# IO_top_board.net
KiCad netlist of a schematic drawn in EAGLE
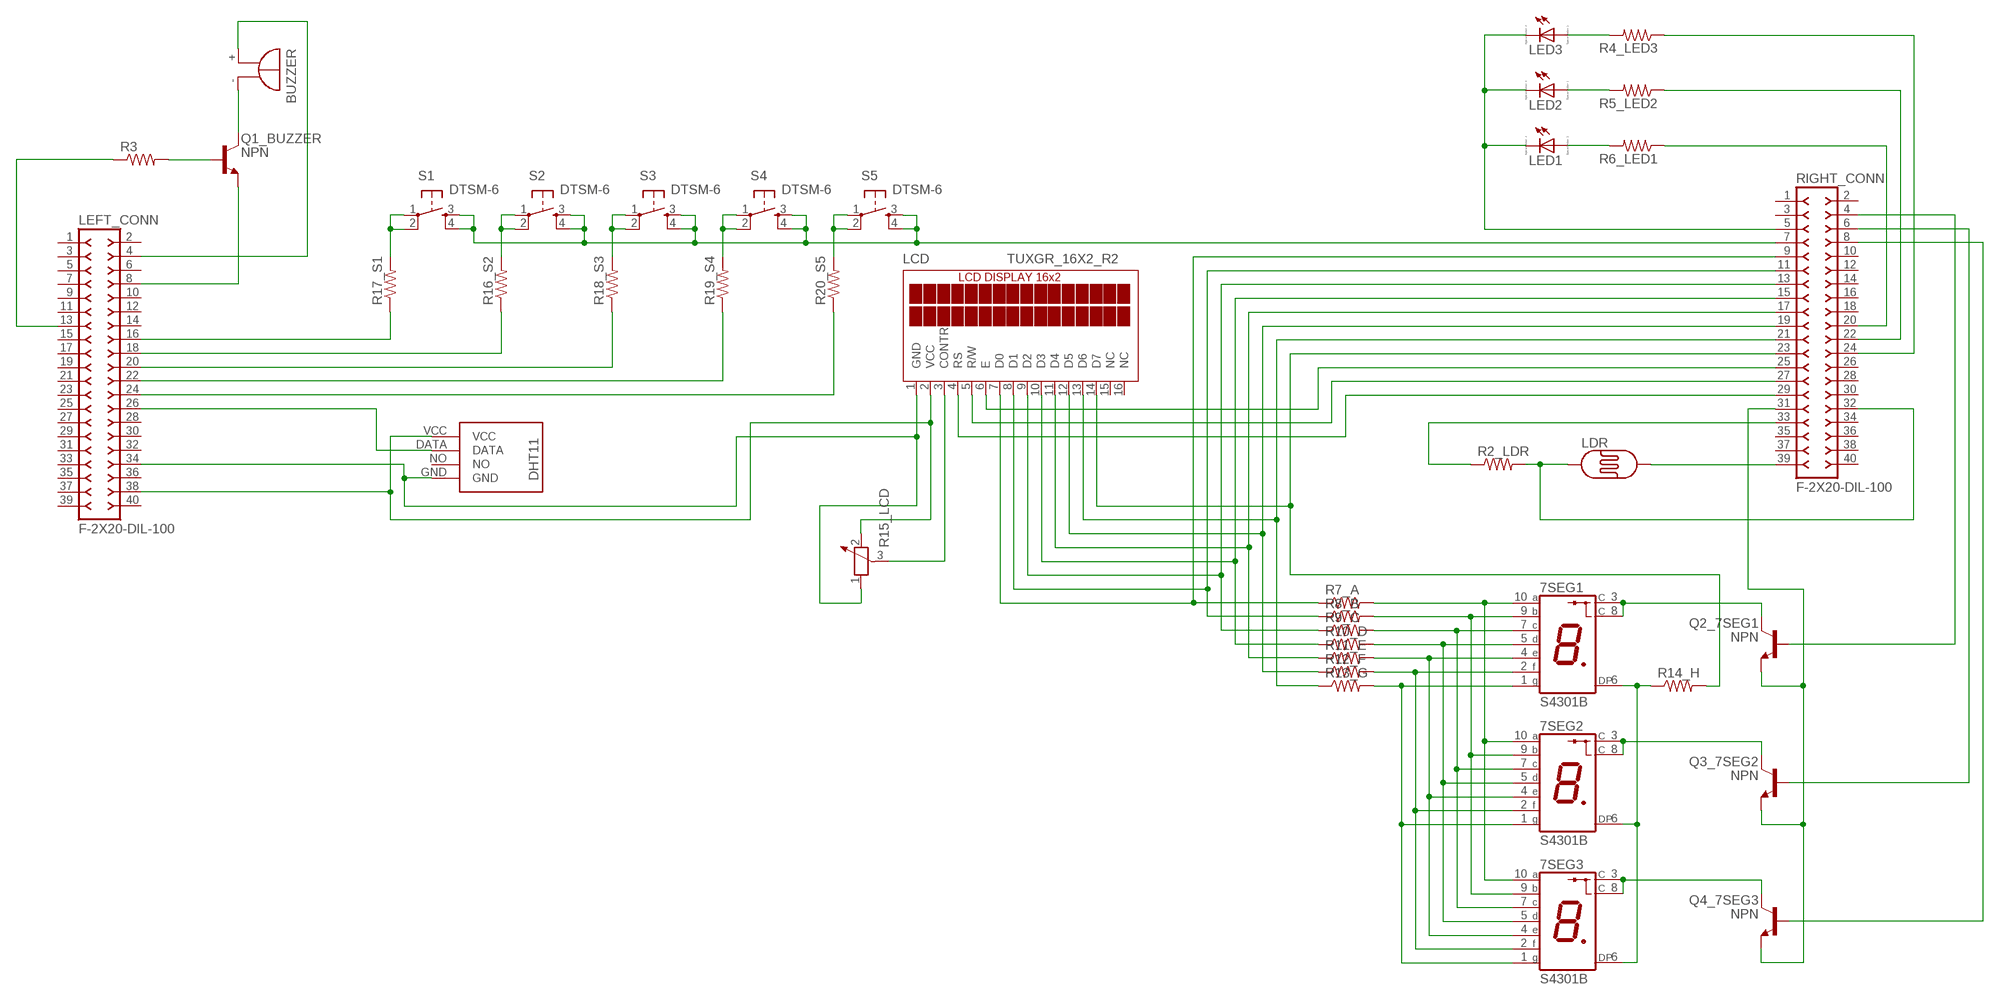
[diagram p0: schematic, sheet 1]

(export (version "E")
  (design (tool "Eeschema 10.0.6"))
  (components
    (comp (ref "7SEG1")
      (value "S4301B")
      (footprint "eagle-import:S4301B")
      (libsource (lib "eagle-import") (part "S4301B"))
    )
    (comp (ref "7SEG2")
      (value "S4301B")
      (footprint "eagle-import:S4301B")
      (libsource (lib "eagle-import") (part "S4301B"))
    )
    (comp (ref "7SEG3")
      (value "S4301B")
      (footprint "eagle-import:S4301B")
      (libsource (lib "eagle-import") (part "S4301B"))
    )
    (comp (ref "BUZZER")
      (value "EB2209A")
      (footprint "eagle-import:EB2209A")
      (libsource (lib "eagle-import") (part "EB2209A"))
    )
    (comp (ref "LCD")
      (value "TUXGR_16X2_R2")
      (footprint "eagle-import:TUXGR_16X2_R2")
      (libsource (lib "eagle-import") (part "TUXGR_16X2_R2"))
    )
    (comp (ref "LDR")
      (value "PHOTOCELLONB")
      (footprint "eagle-import:ON_BOARD")
      (libsource (lib "eagle-import") (part "PHOTOCELLONB"))
    )
    (comp (ref "LED1")
      (value "LED_ELD260")
      (footprint "eagle-import:LED_LD260")
      (libsource (lib "eagle-import") (part "LED_ELD260"))
    )
    (comp (ref "LED2")
      (value "LED_ELD260")
      (footprint "eagle-import:LED_LD260")
      (libsource (lib "eagle-import") (part "LED_ELD260"))
    )
    (comp (ref "LED3")
      (value "LED_ELD260")
      (footprint "eagle-import:LED_LD260")
      (libsource (lib "eagle-import") (part "LED_ELD260"))
    )
    (comp (ref "LEFT_CONN")
      (value "F-2X20-DIL-100")
      (footprint "eagle-import:DIL-100-2X20")
      (libsource (lib "eagle-import") (part "F-2X20-DIL-100"))
    )
    (comp (ref "Q1_BUZZER")
      (value "NPN")
      (footprint "eagle-import:SC70")
      (libsource (lib "eagle-import") (part "NPNSC-70_"))
    )
    (comp (ref "Q2_7SEG1")
      (value "NPN")
      (footprint "eagle-import:SC70")
      (libsource (lib "eagle-import") (part "NPNSC-70_"))
    )
    (comp (ref "Q3_7SEG2")
      (value "NPN")
      (footprint "eagle-import:SC70")
      (libsource (lib "eagle-import") (part "NPNSC-70_"))
    )
    (comp (ref "Q4_7SEG3")
      (value "NPN")
      (footprint "eagle-import:SC70")
      (libsource (lib "eagle-import") (part "NPNSC-70_"))
    )
    (comp (ref "R2_LDR")
      (value "R-US_0204/5")
      (footprint "eagle-import:0204_5")
      (libsource (lib "eagle-import") (part "R-US_0204/5"))
    )
    (comp (ref "R3")
      (value "R-US_0204/5")
      (footprint "eagle-import:0204_5")
      (libsource (lib "eagle-import") (part "R-US_0204/5"))
    )
    (comp (ref "R4_LED3")
      (value "R-US_0204/5")
      (footprint "eagle-import:0204_5")
      (libsource (lib "eagle-import") (part "R-US_0204/5"))
    )
    (comp (ref "R5_LED2")
      (value "R-US_0204/5")
      (footprint "eagle-import:0204_5")
      (libsource (lib "eagle-import") (part "R-US_0204/5"))
    )
    (comp (ref "R6_LED1")
      (value "R-US_0204/5")
      (footprint "eagle-import:0204_5")
      (libsource (lib "eagle-import") (part "R-US_0204/5"))
    )
    (comp (ref "R7_A")
      (value "R-US_0204/5")
      (footprint "eagle-import:0204_5")
      (libsource (lib "eagle-import") (part "R-US_0204/5"))
    )
    (comp (ref "R8_B")
      (value "R-US_0204/5")
      (footprint "eagle-import:0204_5")
      (libsource (lib "eagle-import") (part "R-US_0204/5"))
    )
    (comp (ref "R9_C")
      (value "R-US_0204/5")
      (footprint "eagle-import:0204_5")
      (libsource (lib "eagle-import") (part "R-US_0204/5"))
    )
    (comp (ref "R10_D")
      (value "R-US_0204/5")
      (footprint "eagle-import:0204_5")
      (libsource (lib "eagle-import") (part "R-US_0204/5"))
    )
    (comp (ref "R11_E")
      (value "R-US_0204/5")
      (footprint "eagle-import:0204_5")
      (libsource (lib "eagle-import") (part "R-US_0204/5"))
    )
    (comp (ref "R12_F")
      (value "R-US_0204/5")
      (footprint "eagle-import:0204_5")
      (libsource (lib "eagle-import") (part "R-US_0204/5"))
    )
    (comp (ref "R13_G")
      (value "R-US_0204/5")
      (footprint "eagle-import:0204_5")
      (libsource (lib "eagle-import") (part "R-US_0204/5"))
    )
    (comp (ref "R14_H")
      (value "R-US_0204/5")
      (footprint "eagle-import:0204_5")
      (libsource (lib "eagle-import") (part "R-US_0204/5"))
    )
    (comp (ref "R15_LCD")
      (value "POTENTIOMETER_PT-10")
      (footprint "eagle-import:PT-10")
      (libsource (lib "eagle-import") (part "POTENTIOMETER_PT-10"))
    )
    (comp (ref "R16_S2")
      (value "R-US_0204/5")
      (footprint "eagle-import:0204_5")
      (libsource (lib "eagle-import") (part "R-US_0204/5"))
    )
    (comp (ref "R17_S1")
      (value "R-US_0204/5")
      (footprint "eagle-import:0204_5")
      (libsource (lib "eagle-import") (part "R-US_0204/5"))
    )
    (comp (ref "R18_S3")
      (value "R-US_0204/5")
      (footprint "eagle-import:0204_5")
      (libsource (lib "eagle-import") (part "R-US_0204/5"))
    )
    (comp (ref "R19_S4")
      (value "R-US_0204/5")
      (footprint "eagle-import:0204_5")
      (libsource (lib "eagle-import") (part "R-US_0204/5"))
    )
    (comp (ref "R20_S5")
      (value "R-US_0204/5")
      (footprint "eagle-import:0204_5")
      (libsource (lib "eagle-import") (part "R-US_0204/5"))
    )
    (comp (ref "RIGHT_CONN")
      (value "F-2X20-DIL-100")
      (footprint "eagle-import:DIL-100-2X20")
      (libsource (lib "eagle-import") (part "F-2X20-DIL-100"))
    )
    (comp (ref "S1")
      (value "DTSM-6")
      (footprint "eagle-import:DTSM-6")
      (libsource (lib "eagle-import") (part "DTSM-6"))
    )
    (comp (ref "S2")
      (value "DTSM-6")
      (footprint "eagle-import:DTSM-6")
      (libsource (lib "eagle-import") (part "DTSM-6"))
    )
    (comp (ref "S3")
      (value "DTSM-6")
      (footprint "eagle-import:DTSM-6")
      (libsource (lib "eagle-import") (part "DTSM-6"))
    )
    (comp (ref "S4")
      (value "DTSM-6")
      (footprint "eagle-import:DTSM-6")
      (libsource (lib "eagle-import") (part "DTSM-6"))
    )
    (comp (ref "S5")
      (value "DTSM-6")
      (footprint "eagle-import:DTSM-6")
      (libsource (lib "eagle-import") (part "DTSM-6"))
    )
    (comp (ref "U$1")
      (value "DHT11-PION.")
      (footprint "eagle-import:DHT11-PION.")
      (libsource (lib "eagle-import") (part "DHT11-PION."))
    )
  )
  (nets
    (net (code "1") (name "Net-(7SEG1-A)") (class "Default")
      (node (ref "7SEG1") (pin "10") (pinfunction "A_10") (pintype "passive"))
      (node (ref "7SEG2") (pin "10") (pinfunction "A_10") (pintype "passive"))
      (node (ref "7SEG3") (pin "10") (pinfunction "A_10") (pintype "passive"))
      (node (ref "R7_A") (pin "2") (pinfunction "2_2") (pintype "passive"))
    )
    (net (code "2") (name "Net-(7SEG1-B)") (class "Default")
      (node (ref "7SEG1") (pin "9") (pinfunction "B_9") (pintype "passive"))
      (node (ref "7SEG2") (pin "9") (pinfunction "B_9") (pintype "passive"))
      (node (ref "7SEG3") (pin "9") (pinfunction "B_9") (pintype "passive"))
      (node (ref "R8_B") (pin "2") (pinfunction "2_2") (pintype "passive"))
    )
    (net (code "3") (name "Net-(7SEG1-C-Pad7)") (class "Default")
      (node (ref "7SEG1") (pin "7") (pinfunction "C_7") (pintype "passive"))
      (node (ref "7SEG2") (pin "7") (pinfunction "C_7") (pintype "passive"))
      (node (ref "7SEG3") (pin "7") (pinfunction "C_7") (pintype "passive"))
      (node (ref "R9_C") (pin "2") (pinfunction "2_2") (pintype "passive"))
    )
    (net (code "4") (name "Net-(7SEG1-D)") (class "Default")
      (node (ref "7SEG1") (pin "5") (pinfunction "D_5") (pintype "passive"))
      (node (ref "7SEG2") (pin "5") (pinfunction "D_5") (pintype "passive"))
      (node (ref "7SEG3") (pin "5") (pinfunction "D_5") (pintype "passive"))
      (node (ref "R10_D") (pin "2") (pinfunction "2_2") (pintype "passive"))
    )
    (net (code "5") (name "Net-(7SEG1-DP)") (class "Default")
      (node (ref "7SEG1") (pin "6") (pinfunction "DP_6") (pintype "passive"))
      (node (ref "7SEG2") (pin "6") (pinfunction "DP_6") (pintype "passive"))
      (node (ref "7SEG3") (pin "6") (pinfunction "DP_6") (pintype "passive"))
      (node (ref "R14_H") (pin "1") (pinfunction "1_1") (pintype "passive"))
    )
    (net (code "6") (name "Net-(7SEG1-E)") (class "Default")
      (node (ref "7SEG1") (pin "4") (pinfunction "E_4") (pintype "passive"))
      (node (ref "7SEG2") (pin "4") (pinfunction "E_4") (pintype "passive"))
      (node (ref "7SEG3") (pin "4") (pinfunction "E_4") (pintype "passive"))
      (node (ref "R11_E") (pin "2") (pinfunction "2_2") (pintype "passive"))
    )
    (net (code "7") (name "Net-(7SEG1-F)") (class "Default")
      (node (ref "7SEG1") (pin "2") (pinfunction "F_2") (pintype "passive"))
      (node (ref "7SEG2") (pin "2") (pinfunction "F_2") (pintype "passive"))
      (node (ref "7SEG3") (pin "2") (pinfunction "F_2") (pintype "passive"))
      (node (ref "R12_F") (pin "2") (pinfunction "2_2") (pintype "passive"))
    )
    (net (code "8") (name "Net-(7SEG1-G)") (class "Default")
      (node (ref "7SEG1") (pin "1") (pinfunction "G_1") (pintype "passive"))
      (node (ref "7SEG2") (pin "1") (pinfunction "G_1") (pintype "passive"))
      (node (ref "7SEG3") (pin "1") (pinfunction "G_1") (pintype "passive"))
      (node (ref "R13_G") (pin "2") (pinfunction "2_2") (pintype "passive"))
    )
    (net (code "9") (name "Net-(BUZZER-Pad+)") (class "Default")
      (node (ref "BUZZER") (pin "+") (pinfunction "+_+") (pintype "passive"))
      (node (ref "LEFT_CONN") (pin "4") (pinfunction "4_4") (pintype "passive"))
    )
    (net (code "10") (name "Net-(LCD-CONTR)") (class "Default")
      (node (ref "LCD") (pin "3") (pinfunction "CONTR_3") (pintype "input"))
      (node (ref "R15_LCD") (pin "3") (pinfunction "3_3") (pintype "passive"))
    )
    (net (code "11") (name "Net-(LCD-D0)") (class "Default")
      (node (ref "LCD") (pin "7") (pinfunction "D0_7") (pintype "input"))
      (node (ref "R7_A") (pin "1") (pinfunction "1_1") (pintype "passive"))
      (node (ref "RIGHT_CONN") (pin "9") (pinfunction "9_9") (pintype "passive"))
    )
    (net (code "12") (name "Net-(LCD-D1)") (class "Default")
      (node (ref "LCD") (pin "8") (pinfunction "D1_8") (pintype "input"))
      (node (ref "R8_B") (pin "1") (pinfunction "1_1") (pintype "passive"))
      (node (ref "RIGHT_CONN") (pin "11") (pinfunction "11_11") (pintype "passive"))
    )
    (net (code "13") (name "Net-(LCD-D2)") (class "Default")
      (node (ref "LCD") (pin "9") (pinfunction "D2_9") (pintype "input"))
      (node (ref "R9_C") (pin "1") (pinfunction "1_1") (pintype "passive"))
      (node (ref "RIGHT_CONN") (pin "13") (pinfunction "13_13") (pintype "passive"))
    )
    (net (code "14") (name "Net-(LCD-D3)") (class "Default")
      (node (ref "LCD") (pin "10") (pinfunction "D3_10") (pintype "input"))
      (node (ref "R10_D") (pin "1") (pinfunction "1_1") (pintype "passive"))
      (node (ref "RIGHT_CONN") (pin "15") (pinfunction "15_15") (pintype "passive"))
    )
    (net (code "15") (name "Net-(LCD-D4)") (class "Default")
      (node (ref "LCD") (pin "11") (pinfunction "D4_11") (pintype "input"))
      (node (ref "R11_E") (pin "1") (pinfunction "1_1") (pintype "passive"))
      (node (ref "RIGHT_CONN") (pin "17") (pinfunction "17_17") (pintype "passive"))
    )
    (net (code "16") (name "Net-(LCD-D5)") (class "Default")
      (node (ref "LCD") (pin "12") (pinfunction "D5_12") (pintype "input"))
      (node (ref "R12_F") (pin "1") (pinfunction "1_1") (pintype "passive"))
      (node (ref "RIGHT_CONN") (pin "19") (pinfunction "19_19") (pintype "passive"))
    )
    (net (code "17") (name "Net-(LCD-D6)") (class "Default")
      (node (ref "LCD") (pin "13") (pinfunction "D6_13") (pintype "input"))
      (node (ref "R13_G") (pin "1") (pinfunction "1_1") (pintype "passive"))
      (node (ref "RIGHT_CONN") (pin "21") (pinfunction "21_21") (pintype "passive"))
    )
    (net (code "18") (name "Net-(LCD-D7)") (class "Default")
      (node (ref "LCD") (pin "14") (pinfunction "D7_14") (pintype "input"))
      (node (ref "R14_H") (pin "2") (pinfunction "2_2") (pintype "passive"))
      (node (ref "RIGHT_CONN") (pin "23") (pinfunction "23_23") (pintype "passive"))
    )
    (net (code "19") (name "Net-(LCD-E)") (class "Default")
      (node (ref "LCD") (pin "6") (pinfunction "E_6") (pintype "input"))
      (node (ref "RIGHT_CONN") (pin "25") (pinfunction "25_25") (pintype "passive"))
    )
    (net (code "20") (name "Net-(LCD-GND)") (class "Default")
      (node (ref "LCD") (pin "1") (pinfunction "GND_1") (pintype "power_in"))
      (node (ref "LEFT_CONN") (pin "34") (pinfunction "34_34") (pintype "passive"))
      (node (ref "R15_LCD") (pin "1") (pinfunction "1_1") (pintype "passive"))
      (node (ref "U$1") (pin "GND") (pinfunction "GND_GND") (pintype "bidirectional"))
    )
    (net (code "21") (name "Net-(LCD-RS)") (class "Default")
      (node (ref "LCD") (pin "4") (pinfunction "RS_4") (pintype "input"))
      (node (ref "RIGHT_CONN") (pin "29") (pinfunction "29_29") (pintype "passive"))
    )
    (net (code "22") (name "Net-(LCD-R{slash}W)") (class "Default")
      (node (ref "LCD") (pin "5") (pinfunction "R/W_5") (pintype "input"))
      (node (ref "RIGHT_CONN") (pin "27") (pinfunction "27_27") (pintype "passive"))
    )
    (net (code "23") (name "Net-(LCD-VCC)") (class "Default")
      (node (ref "LCD") (pin "2") (pinfunction "VCC_2") (pintype "power_in"))
      (node (ref "LEFT_CONN") (pin "38") (pinfunction "38_38") (pintype "passive"))
      (node (ref "R15_LCD") (pin "2") (pinfunction "2_2") (pintype "passive"))
      (node (ref "U$1") (pin "VCC") (pinfunction "VCC_VCC") (pintype "bidirectional"))
    )
    (net (code "24") (name "Net-(LDR-P$1)") (class "Default")
      (node (ref "LDR") (pin "1") (pinfunction "P$1_1") (pintype "bidirectional"))
      (node (ref "R2_LDR") (pin "2") (pinfunction "2_2") (pintype "passive"))
      (node (ref "RIGHT_CONN") (pin "32") (pinfunction "32_32") (pintype "passive"))
    )
    (net (code "25") (name "Net-(LDR-P$2)") (class "Default")
      (node (ref "LDR") (pin "2") (pinfunction "P$2_2") (pintype "bidirectional"))
      (node (ref "RIGHT_CONN") (pin "39") (pinfunction "39_39") (pintype "passive"))
    )
    (net (code "26") (name "Net-(LED1-C)") (class "Default")
      (node (ref "LED1") (pin "K") (pinfunction "C_K") (pintype "passive"))
      (node (ref "LED2") (pin "K") (pinfunction "C_K") (pintype "passive"))
      (node (ref "LED3") (pin "K") (pinfunction "C_K") (pintype "passive"))
      (node (ref "RIGHT_CONN") (pin "5") (pinfunction "5_5") (pintype "passive"))
    )
    (net (code "27") (name "Net-(LED1-PadA)") (class "Default")
      (node (ref "LED1") (pin "A") (pinfunction "A_A") (pintype "passive"))
      (node (ref "R6_LED1") (pin "2") (pinfunction "2_2") (pintype "passive"))
    )
    (net (code "28") (name "Net-(LED2-PadA)") (class "Default")
      (node (ref "LED2") (pin "A") (pinfunction "A_A") (pintype "passive"))
      (node (ref "R5_LED2") (pin "2") (pinfunction "2_2") (pintype "passive"))
    )
    (net (code "29") (name "Net-(LED3-PadA)") (class "Default")
      (node (ref "LED3") (pin "A") (pinfunction "A_A") (pintype "passive"))
      (node (ref "R4_LED3") (pin "2") (pinfunction "2_2") (pintype "passive"))
    )
    (net (code "30") (name "Net-(LEFT_CONN-Pad13)") (class "Default")
      (node (ref "LEFT_CONN") (pin "13") (pinfunction "13_13") (pintype "passive"))
      (node (ref "R3") (pin "1") (pinfunction "1_1") (pintype "passive"))
    )
    (net (code "31") (name "Net-(LEFT_CONN-Pad16)") (class "Default")
      (node (ref "LEFT_CONN") (pin "16") (pinfunction "16_16") (pintype "passive"))
      (node (ref "R17_S1") (pin "1") (pinfunction "1_1") (pintype "passive"))
    )
    (net (code "32") (name "Net-(LEFT_CONN-Pad18)") (class "Default")
      (node (ref "LEFT_CONN") (pin "18") (pinfunction "18_18") (pintype "passive"))
      (node (ref "R16_S2") (pin "1") (pinfunction "1_1") (pintype "passive"))
    )
    (net (code "33") (name "Net-(LEFT_CONN-Pad20)") (class "Default")
      (node (ref "LEFT_CONN") (pin "20") (pinfunction "20_20") (pintype "passive"))
      (node (ref "R18_S3") (pin "1") (pinfunction "1_1") (pintype "passive"))
    )
    (net (code "34") (name "Net-(LEFT_CONN-Pad22)") (class "Default")
      (node (ref "LEFT_CONN") (pin "22") (pinfunction "22_22") (pintype "passive"))
      (node (ref "R19_S4") (pin "1") (pinfunction "1_1") (pintype "passive"))
    )
    (net (code "35") (name "Net-(LEFT_CONN-Pad24)") (class "Default")
      (node (ref "LEFT_CONN") (pin "24") (pinfunction "24_24") (pintype "passive"))
      (node (ref "R20_S5") (pin "1") (pinfunction "1_1") (pintype "passive"))
    )
    (net (code "36") (name "Net-(LEFT_CONN-Pad26)") (class "Default")
      (node (ref "LEFT_CONN") (pin "26") (pinfunction "26_26") (pintype "passive"))
      (node (ref "U$1") (pin "DATA") (pinfunction "DATA_DATA") (pintype "bidirectional"))
    )
    (net (code "37") (name "Net-(Q1_BUZZER-B)") (class "Default")
      (node (ref "Q1_BUZZER") (pin "2") (pinfunction "B_2") (pintype "passive"))
      (node (ref "R3") (pin "2") (pinfunction "2_2") (pintype "passive"))
    )
    (net (code "38") (name "Net-(Q1_BUZZER-C)") (class "Default")
      (node (ref "BUZZER") (pin "-") (pinfunction "-_-") (pintype "passive"))
      (node (ref "Q1_BUZZER") (pin "3") (pinfunction "C_3") (pintype "passive"))
    )
    (net (code "39") (name "Net-(Q1_BUZZER-E)") (class "Default")
      (node (ref "LEFT_CONN") (pin "8") (pinfunction "8_8") (pintype "passive"))
      (node (ref "Q1_BUZZER") (pin "1") (pinfunction "E_1") (pintype "passive"))
    )
    (net (code "40") (name "Net-(Q2_7SEG1-B)") (class "Default")
      (node (ref "Q2_7SEG1") (pin "2") (pinfunction "B_2") (pintype "passive"))
      (node (ref "RIGHT_CONN") (pin "4") (pinfunction "4_4") (pintype "passive"))
    )
    (net (code "41") (name "Net-(Q2_7SEG1-C)") (class "Default")
      (node (ref "7SEG1") (pin "3") (pinfunction "C_3") (pintype "passive"))
      (node (ref "7SEG1") (pin "8") (pinfunction "C_8") (pintype "passive"))
      (node (ref "Q2_7SEG1") (pin "3") (pinfunction "C_3") (pintype "passive"))
    )
    (net (code "42") (name "Net-(Q2_7SEG1-E)") (class "Default")
      (node (ref "Q2_7SEG1") (pin "1") (pinfunction "E_1") (pintype "passive"))
      (node (ref "Q3_7SEG2") (pin "1") (pinfunction "E_1") (pintype "passive"))
      (node (ref "Q4_7SEG3") (pin "1") (pinfunction "E_1") (pintype "passive"))
      (node (ref "RIGHT_CONN") (pin "31") (pinfunction "31_31") (pintype "passive"))
    )
    (net (code "43") (name "Net-(Q3_7SEG2-B)") (class "Default")
      (node (ref "Q3_7SEG2") (pin "2") (pinfunction "B_2") (pintype "passive"))
      (node (ref "RIGHT_CONN") (pin "6") (pinfunction "6_6") (pintype "passive"))
    )
    (net (code "44") (name "Net-(Q3_7SEG2-C)") (class "Default")
      (node (ref "7SEG2") (pin "3") (pinfunction "C_3") (pintype "passive"))
      (node (ref "7SEG2") (pin "8") (pinfunction "C_8") (pintype "passive"))
      (node (ref "Q3_7SEG2") (pin "3") (pinfunction "C_3") (pintype "passive"))
    )
    (net (code "45") (name "Net-(Q4_7SEG3-B)") (class "Default")
      (node (ref "Q4_7SEG3") (pin "2") (pinfunction "B_2") (pintype "passive"))
      (node (ref "RIGHT_CONN") (pin "8") (pinfunction "8_8") (pintype "passive"))
    )
    (net (code "46") (name "Net-(Q4_7SEG3-C)") (class "Default")
      (node (ref "7SEG3") (pin "3") (pinfunction "C_3") (pintype "passive"))
      (node (ref "7SEG3") (pin "8") (pinfunction "C_8") (pintype "passive"))
      (node (ref "Q4_7SEG3") (pin "3") (pinfunction "C_3") (pintype "passive"))
    )
    (net (code "47") (name "Net-(R2_LDR-Pad1)") (class "Default")
      (node (ref "R2_LDR") (pin "1") (pinfunction "1_1") (pintype "passive"))
      (node (ref "RIGHT_CONN") (pin "33") (pinfunction "33_33") (pintype "passive"))
    )
    (net (code "48") (name "Net-(R4_LED3-Pad1)") (class "Default")
      (node (ref "R4_LED3") (pin "1") (pinfunction "1_1") (pintype "passive"))
      (node (ref "RIGHT_CONN") (pin "24") (pinfunction "24_24") (pintype "passive"))
    )
    (net (code "49") (name "Net-(R5_LED2-Pad1)") (class "Default")
      (node (ref "R5_LED2") (pin "1") (pinfunction "1_1") (pintype "passive"))
      (node (ref "RIGHT_CONN") (pin "22") (pinfunction "22_22") (pintype "passive"))
    )
    (net (code "50") (name "Net-(R6_LED1-Pad1)") (class "Default")
      (node (ref "R6_LED1") (pin "1") (pinfunction "1_1") (pintype "passive"))
      (node (ref "RIGHT_CONN") (pin "20") (pinfunction "20_20") (pintype "passive"))
    )
    (net (code "51") (name "Net-(R16_S2-Pad2)") (class "Default")
      (node (ref "R16_S2") (pin "2") (pinfunction "2_2") (pintype "passive"))
      (node (ref "S2") (pin "1") (pinfunction "1_1") (pintype "passive"))
      (node (ref "S2") (pin "2") (pinfunction "2_2") (pintype "passive"))
    )
    (net (code "52") (name "Net-(R17_S1-Pad2)") (class "Default")
      (node (ref "R17_S1") (pin "2") (pinfunction "2_2") (pintype "passive"))
      (node (ref "S1") (pin "1") (pinfunction "1_1") (pintype "passive"))
      (node (ref "S1") (pin "2") (pinfunction "2_2") (pintype "passive"))
    )
    (net (code "53") (name "Net-(R18_S3-Pad2)") (class "Default")
      (node (ref "R18_S3") (pin "2") (pinfunction "2_2") (pintype "passive"))
      (node (ref "S3") (pin "1") (pinfunction "1_1") (pintype "passive"))
      (node (ref "S3") (pin "2") (pinfunction "2_2") (pintype "passive"))
    )
    (net (code "54") (name "Net-(R19_S4-Pad2)") (class "Default")
      (node (ref "R19_S4") (pin "2") (pinfunction "2_2") (pintype "passive"))
      (node (ref "S4") (pin "1") (pinfunction "1_1") (pintype "passive"))
      (node (ref "S4") (pin "2") (pinfunction "2_2") (pintype "passive"))
    )
    (net (code "55") (name "Net-(R20_S5-Pad2)") (class "Default")
      (node (ref "R20_S5") (pin "2") (pinfunction "2_2") (pintype "passive"))
      (node (ref "S5") (pin "1") (pinfunction "1_1") (pintype "passive"))
      (node (ref "S5") (pin "2") (pinfunction "2_2") (pintype "passive"))
    )
    (net (code "56") (name "Net-(RIGHT_CONN-Pad7)") (class "Default")
      (node (ref "RIGHT_CONN") (pin "7") (pinfunction "7_7") (pintype "passive"))
      (node (ref "S1") (pin "3") (pinfunction "3_3") (pintype "passive"))
      (node (ref "S1") (pin "4") (pinfunction "4_4") (pintype "passive"))
      (node (ref "S2") (pin "3") (pinfunction "3_3") (pintype "passive"))
      (node (ref "S2") (pin "4") (pinfunction "4_4") (pintype "passive"))
      (node (ref "S3") (pin "3") (pinfunction "3_3") (pintype "passive"))
      (node (ref "S3") (pin "4") (pinfunction "4_4") (pintype "passive"))
      (node (ref "S4") (pin "3") (pinfunction "3_3") (pintype "passive"))
      (node (ref "S4") (pin "4") (pinfunction "4_4") (pintype "passive"))
      (node (ref "S5") (pin "3") (pinfunction "3_3") (pintype "passive"))
      (node (ref "S5") (pin "4") (pinfunction "4_4") (pintype "passive"))
    )
    (net (code "57") (name "unconnected-(LCD-NC-Pad15)") (class "Default")
      (node (ref "LCD") (pin "15") (pinfunction "NC_15") (pintype "no_connect"))
    )
    (net (code "58") (name "unconnected-(LCD-NC-Pad16)") (class "Default")
      (node (ref "LCD") (pin "16") (pinfunction "NC_16") (pintype "no_connect"))
    )
    (net (code "59") (name "unconnected-(LEFT_CONN-Pad1)") (class "Default")
      (node (ref "LEFT_CONN") (pin "1") (pinfunction "1_1") (pintype "passive"))
    )
    (net (code "60") (name "unconnected-(LEFT_CONN-Pad2)") (class "Default")
      (node (ref "LEFT_CONN") (pin "2") (pinfunction "2_2") (pintype "passive"))
    )
    (net (code "61") (name "unconnected-(LEFT_CONN-Pad3)") (class "Default")
      (node (ref "LEFT_CONN") (pin "3") (pinfunction "3_3") (pintype "passive"))
    )
    (net (code "62") (name "unconnected-(LEFT_CONN-Pad5)") (class "Default")
      (node (ref "LEFT_CONN") (pin "5") (pinfunction "5_5") (pintype "passive"))
    )
    (net (code "63") (name "unconnected-(LEFT_CONN-Pad6)") (class "Default")
      (node (ref "LEFT_CONN") (pin "6") (pinfunction "6_6") (pintype "passive"))
    )
    (net (code "64") (name "unconnected-(LEFT_CONN-Pad7)") (class "Default")
      (node (ref "LEFT_CONN") (pin "7") (pinfunction "7_7") (pintype "passive"))
    )
    (net (code "65") (name "unconnected-(LEFT_CONN-Pad9)") (class "Default")
      (node (ref "LEFT_CONN") (pin "9") (pinfunction "9_9") (pintype "passive"))
    )
    (net (code "66") (name "unconnected-(LEFT_CONN-Pad10)") (class "Default")
      (node (ref "LEFT_CONN") (pin "10") (pinfunction "10_10") (pintype "passive"))
    )
    (net (code "67") (name "unconnected-(LEFT_CONN-Pad11)") (class "Default")
      (node (ref "LEFT_CONN") (pin "11") (pinfunction "11_11") (pintype "passive"))
    )
    (net (code "68") (name "unconnected-(LEFT_CONN-Pad12)") (class "Default")
      (node (ref "LEFT_CONN") (pin "12") (pinfunction "12_12") (pintype "passive"))
    )
    (net (code "69") (name "unconnected-(LEFT_CONN-Pad14)") (class "Default")
      (node (ref "LEFT_CONN") (pin "14") (pinfunction "14_14") (pintype "passive"))
    )
    (net (code "70") (name "unconnected-(LEFT_CONN-Pad15)") (class "Default")
      (node (ref "LEFT_CONN") (pin "15") (pinfunction "15_15") (pintype "passive"))
    )
    (net (code "71") (name "unconnected-(LEFT_CONN-Pad17)") (class "Default")
      (node (ref "LEFT_CONN") (pin "17") (pinfunction "17_17") (pintype "passive"))
    )
    (net (code "72") (name "unconnected-(LEFT_CONN-Pad19)") (class "Default")
      (node (ref "LEFT_CONN") (pin "19") (pinfunction "19_19") (pintype "passive"))
    )
    (net (code "73") (name "unconnected-(LEFT_CONN-Pad21)") (class "Default")
      (node (ref "LEFT_CONN") (pin "21") (pinfunction "21_21") (pintype "passive"))
    )
    (net (code "74") (name "unconnected-(LEFT_CONN-Pad23)") (class "Default")
      (node (ref "LEFT_CONN") (pin "23") (pinfunction "23_23") (pintype "passive"))
    )
    (net (code "75") (name "unconnected-(LEFT_CONN-Pad25)") (class "Default")
      (node (ref "LEFT_CONN") (pin "25") (pinfunction "25_25") (pintype "passive"))
    )
    (net (code "76") (name "unconnected-(LEFT_CONN-Pad27)") (class "Default")
      (node (ref "LEFT_CONN") (pin "27") (pinfunction "27_27") (pintype "passive"))
    )
    (net (code "77") (name "unconnected-(LEFT_CONN-Pad28)") (class "Default")
      (node (ref "LEFT_CONN") (pin "28") (pinfunction "28_28") (pintype "passive"))
    )
    (net (code "78") (name "unconnected-(LEFT_CONN-Pad29)") (class "Default")
      (node (ref "LEFT_CONN") (pin "29") (pinfunction "29_29") (pintype "passive"))
    )
    (net (code "79") (name "unconnected-(LEFT_CONN-Pad30)") (class "Default")
      (node (ref "LEFT_CONN") (pin "30") (pinfunction "30_30") (pintype "passive"))
    )
    (net (code "80") (name "unconnected-(LEFT_CONN-Pad31)") (class "Default")
      (node (ref "LEFT_CONN") (pin "31") (pinfunction "31_31") (pintype "passive"))
    )
    (net (code "81") (name "unconnected-(LEFT_CONN-Pad32)") (class "Default")
      (node (ref "LEFT_CONN") (pin "32") (pinfunction "32_32") (pintype "passive"))
    )
    (net (code "82") (name "unconnected-(LEFT_CONN-Pad33)") (class "Default")
      (node (ref "LEFT_CONN") (pin "33") (pinfunction "33_33") (pintype "passive"))
    )
    (net (code "83") (name "unconnected-(LEFT_CONN-Pad35)") (class "Default")
      (node (ref "LEFT_CONN") (pin "35") (pinfunction "35_35") (pintype "passive"))
    )
    (net (code "84") (name "unconnected-(LEFT_CONN-Pad36)") (class "Default")
      (node (ref "LEFT_CONN") (pin "36") (pinfunction "36_36") (pintype "passive"))
    )
    (net (code "85") (name "unconnected-(LEFT_CONN-Pad37)") (class "Default")
      (node (ref "LEFT_CONN") (pin "37") (pinfunction "37_37") (pintype "passive"))
    )
    (net (code "86") (name "unconnected-(LEFT_CONN-Pad39)") (class "Default")
      (node (ref "LEFT_CONN") (pin "39") (pinfunction "39_39") (pintype "passive"))
    )
    (net (code "87") (name "unconnected-(LEFT_CONN-Pad40)") (class "Default")
      (node (ref "LEFT_CONN") (pin "40") (pinfunction "40_40") (pintype "passive"))
    )
    (net (code "88") (name "unconnected-(RIGHT_CONN-Pad1)") (class "Default")
      (node (ref "RIGHT_CONN") (pin "1") (pinfunction "1_1") (pintype "passive"))
    )
    (net (code "89") (name "unconnected-(RIGHT_CONN-Pad2)") (class "Default")
      (node (ref "RIGHT_CONN") (pin "2") (pinfunction "2_2") (pintype "passive"))
    )
    (net (code "90") (name "unconnected-(RIGHT_CONN-Pad3)") (class "Default")
      (node (ref "RIGHT_CONN") (pin "3") (pinfunction "3_3") (pintype "passive"))
    )
    (net (code "91") (name "unconnected-(RIGHT_CONN-Pad10)") (class "Default")
      (node (ref "RIGHT_CONN") (pin "10") (pinfunction "10_10") (pintype "passive"))
    )
    (net (code "92") (name "unconnected-(RIGHT_CONN-Pad12)") (class "Default")
      (node (ref "RIGHT_CONN") (pin "12") (pinfunction "12_12") (pintype "passive"))
    )
    (net (code "93") (name "unconnected-(RIGHT_CONN-Pad14)") (class "Default")
      (node (ref "RIGHT_CONN") (pin "14") (pinfunction "14_14") (pintype "passive"))
    )
    (net (code "94") (name "unconnected-(RIGHT_CONN-Pad16)") (class "Default")
      (node (ref "RIGHT_CONN") (pin "16") (pinfunction "16_16") (pintype "passive"))
    )
    (net (code "95") (name "unconnected-(RIGHT_CONN-Pad18)") (class "Default")
      (node (ref "RIGHT_CONN") (pin "18") (pinfunction "18_18") (pintype "passive"))
    )
    (net (code "96") (name "unconnected-(RIGHT_CONN-Pad26)") (class "Default")
      (node (ref "RIGHT_CONN") (pin "26") (pinfunction "26_26") (pintype "passive"))
    )
    (net (code "97") (name "unconnected-(RIGHT_CONN-Pad28)") (class "Default")
      (node (ref "RIGHT_CONN") (pin "28") (pinfunction "28_28") (pintype "passive"))
    )
    (net (code "98") (name "unconnected-(RIGHT_CONN-Pad30)") (class "Default")
      (node (ref "RIGHT_CONN") (pin "30") (pinfunction "30_30") (pintype "passive"))
    )
    (net (code "99") (name "unconnected-(RIGHT_CONN-Pad34)") (class "Default")
      (node (ref "RIGHT_CONN") (pin "34") (pinfunction "34_34") (pintype "passive"))
    )
    (net (code "100") (name "unconnected-(RIGHT_CONN-Pad35)") (class "Default")
      (node (ref "RIGHT_CONN") (pin "35") (pinfunction "35_35") (pintype "passive"))
    )
    (net (code "101") (name "unconnected-(RIGHT_CONN-Pad36)") (class "Default")
      (node (ref "RIGHT_CONN") (pin "36") (pinfunction "36_36") (pintype "passive"))
    )
    (net (code "102") (name "unconnected-(RIGHT_CONN-Pad37)") (class "Default")
      (node (ref "RIGHT_CONN") (pin "37") (pinfunction "37_37") (pintype "passive"))
    )
    (net (code "103") (name "unconnected-(RIGHT_CONN-Pad38)") (class "Default")
      (node (ref "RIGHT_CONN") (pin "38") (pinfunction "38_38") (pintype "passive"))
    )
    (net (code "104") (name "unconnected-(RIGHT_CONN-Pad40)") (class "Default")
      (node (ref "RIGHT_CONN") (pin "40") (pinfunction "40_40") (pintype "passive"))
    )
    (net (code "105") (name "unconnected-(U$1-PadNO)") (class "Default")
      (node (ref "U$1") (pin "NO") (pinfunction "NO_NO") (pintype "bidirectional"))
    )
  )
)
